# item_2022_Frontend_02.net
KiCad netlist of a schematic drawn in EAGLE
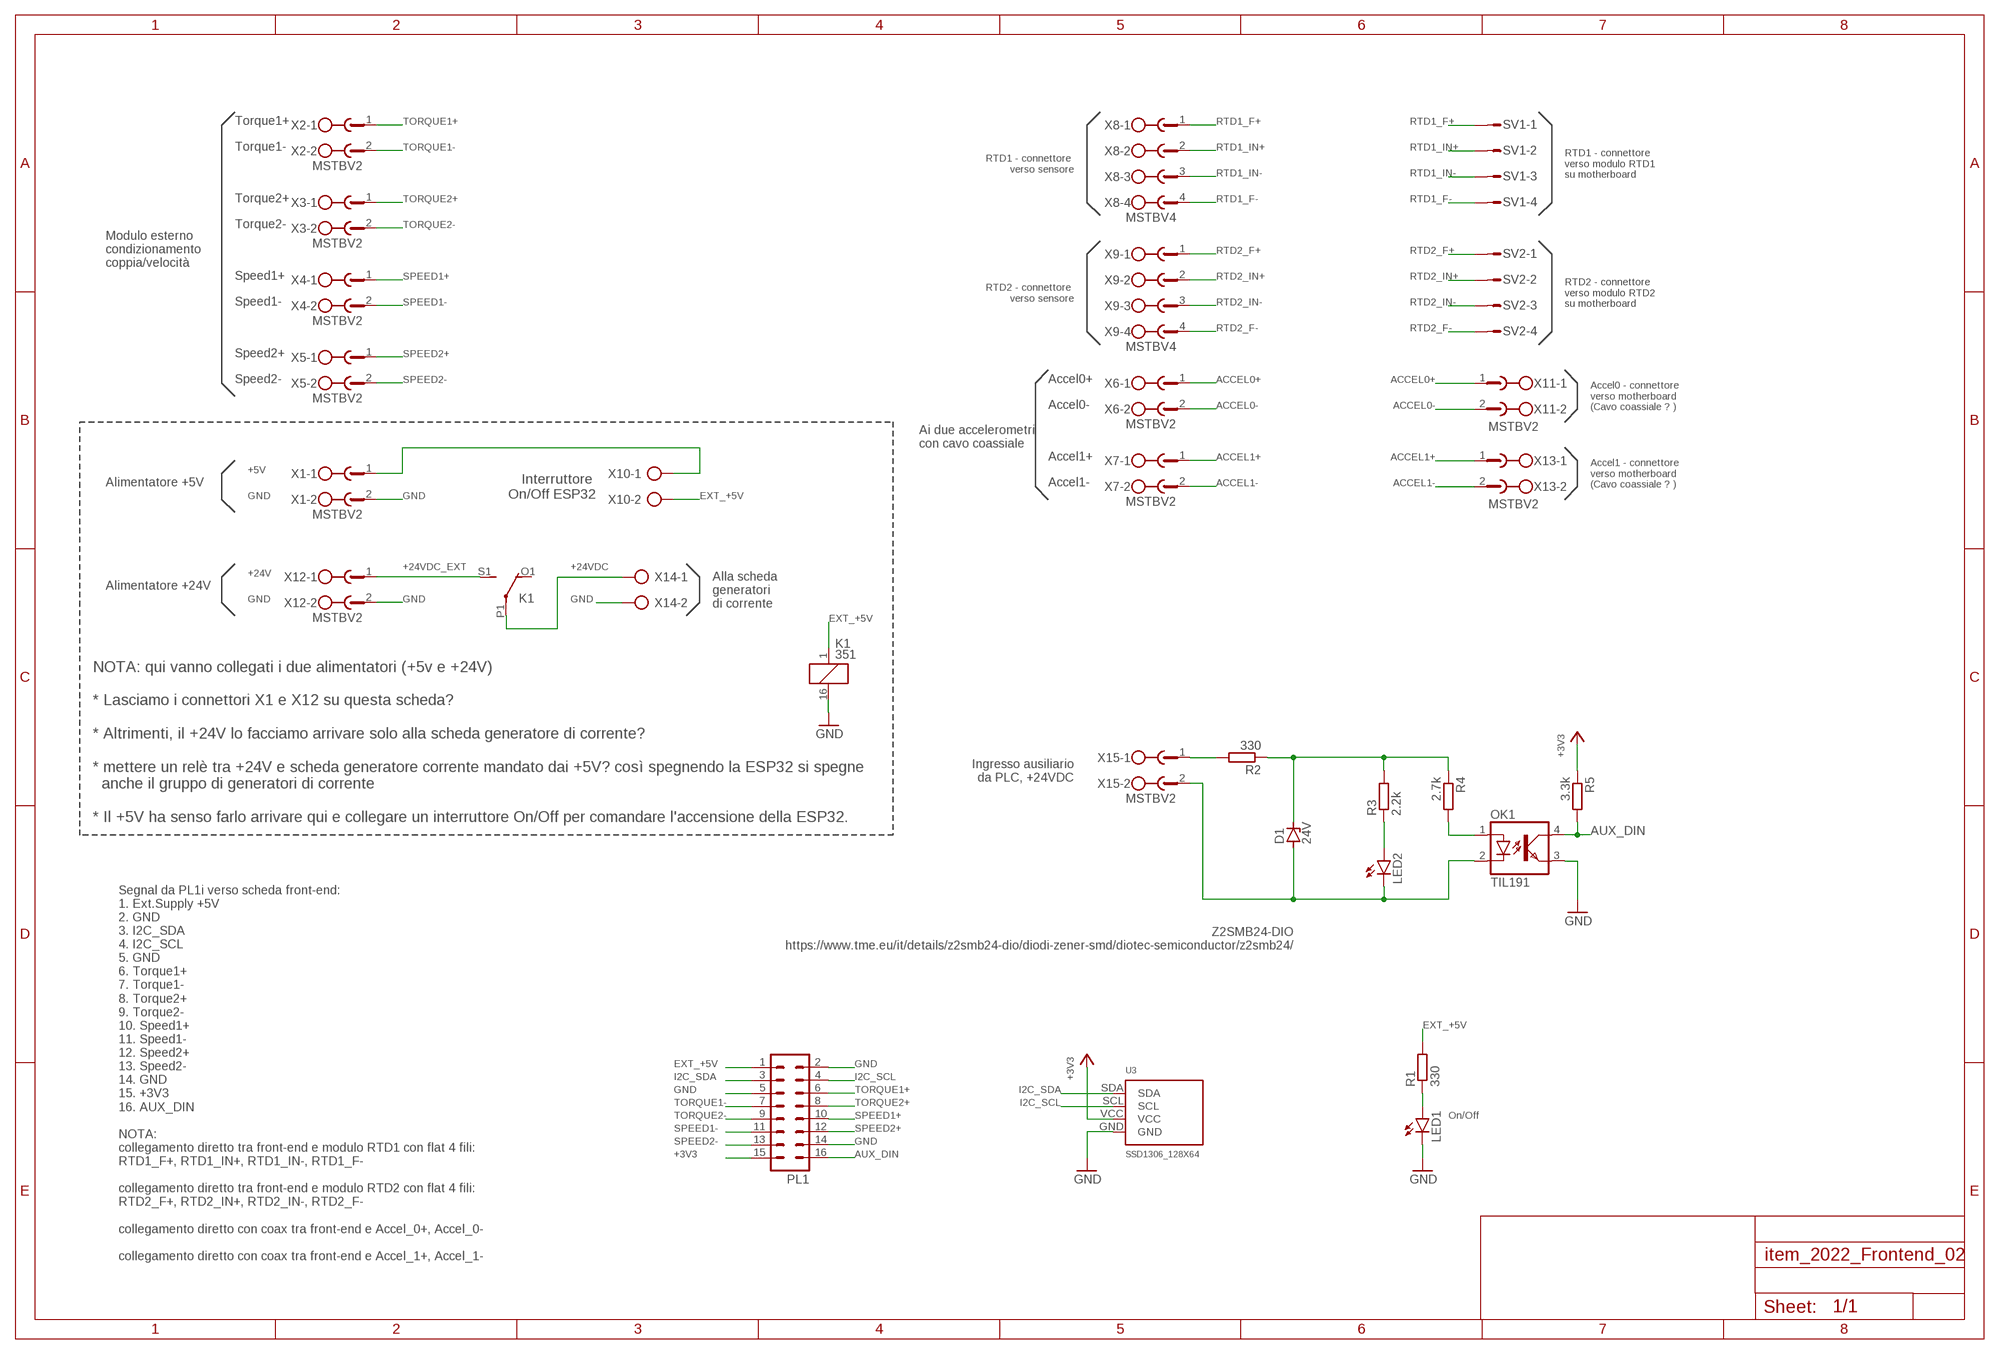
[diagram p0: schematic, sheet 1]

(export (version "E")
  (design (tool "Eeschema 10.0.6"))
  (components
    (comp (ref "D1")
      (value "24V")
      (footprint "eagle-import:SMB")
      (libsource (lib "eagle-import") (part "ZENER-DIODESMB"))
    )
    (comp (ref "K1")
      (value "351")
      (footprint "eagle-import:351")
      (libsource (lib "eagle-import") (part "351"))
    )
    (comp (ref "LED1")
      (value "LED5MM")
      (footprint "eagle-import:LED5MM")
      (libsource (lib "eagle-import") (part "LED5MM"))
    )
    (comp (ref "LED2")
      (value "LED5MM")
      (footprint "eagle-import:LED5MM")
      (libsource (lib "eagle-import") (part "LED5MM"))
    )
    (comp (ref "OK1")
      (value "TIL191")
      (footprint "eagle-import:DIL04")
      (libsource (lib "eagle-import") (part "TIL191"))
    )
    (comp (ref "PL1")
      (value "16V")
      (footprint "eagle-import:16V")
      (libsource (lib "eagle-import") (part "16V"))
    )
    (comp (ref "R1")
      (value "330")
      (footprint "eagle-import:R0805")
      (libsource (lib "eagle-import") (part "R-EU_R0805"))
    )
    (comp (ref "R2")
      (value "330")
      (footprint "eagle-import:R0805")
      (libsource (lib "eagle-import") (part "R-EU_R0805"))
    )
    (comp (ref "R3")
      (value "2.2k")
      (footprint "eagle-import:R0805")
      (libsource (lib "eagle-import") (part "R-EU_R0805"))
    )
    (comp (ref "R4")
      (value "2.7k")
      (footprint "eagle-import:R0805")
      (libsource (lib "eagle-import") (part "R-EU_R0805"))
    )
    (comp (ref "R5")
      (value "3.3k")
      (footprint "eagle-import:R0805")
      (libsource (lib "eagle-import") (part "R-EU_R0805"))
    )
    (comp (ref "SV1")
      (value "S04P")
      (footprint "eagle-import:S04P")
      (libsource (lib "eagle-import") (part "S04P"))
    )
    (comp (ref "SV2")
      (value "S04P")
      (footprint "eagle-import:S04P")
      (libsource (lib "eagle-import") (part "S04P"))
    )
    (comp (ref "U3")
      (value "SSD1306_128X64")
      (footprint "eagle-import:128X64")
      (libsource (lib "eagle-import") (part "SSD1306_128X64"))
    )
    (comp (ref "X1")
      (value "MSTBV2")
      (footprint "eagle-import:MSTBV2")
      (fields (field (name "MPN") "MSTBV 2,5/2-GF-5.08"))
      (libsource (lib "eagle-import") (part "MSTBV2"))
    )
    (comp (ref "X2")
      (value "MSTBV2")
      (footprint "eagle-import:MSTBV2")
      (fields (field (name "MPN") "MSTBV 2,5/2-GF-5.08"))
      (libsource (lib "eagle-import") (part "MSTBV2"))
    )
    (comp (ref "X3")
      (value "MSTBV2")
      (footprint "eagle-import:MSTBV2")
      (fields (field (name "MPN") "MSTBV 2,5/2-GF-5.08"))
      (libsource (lib "eagle-import") (part "MSTBV2"))
    )
    (comp (ref "X4")
      (value "MSTBV2")
      (footprint "eagle-import:MSTBV2")
      (fields (field (name "MPN") "MSTBV 2,5/2-GF-5.08"))
      (libsource (lib "eagle-import") (part "MSTBV2"))
    )
    (comp (ref "X5")
      (value "MSTBV2")
      (footprint "eagle-import:MSTBV2")
      (fields (field (name "MPN") "MSTBV 2,5/2-GF-5.08"))
      (libsource (lib "eagle-import") (part "MSTBV2"))
    )
    (comp (ref "X6")
      (value "MSTBV2")
      (footprint "eagle-import:MSTBV2")
      (fields (field (name "MPN") "MSTBV 2,5/2-GF-5.08"))
      (libsource (lib "eagle-import") (part "MSTBV2"))
    )
    (comp (ref "X7")
      (value "MSTBV2")
      (footprint "eagle-import:MSTBV2")
      (fields (field (name "MPN") "MSTBV 2,5/2-GF-5.08"))
      (libsource (lib "eagle-import") (part "MSTBV2"))
    )
    (comp (ref "X8")
      (value "MSTBV4")
      (footprint "eagle-import:MSTBV4")
      (fields (field (name "MPN") "MSTBV 2,5/4-GF-5.08"))
      (libsource (lib "eagle-import") (part "MSTBV4"))
    )
    (comp (ref "X9")
      (value "MSTBV4")
      (footprint "eagle-import:MSTBV4")
      (fields (field (name "MPN") "MSTBV 2,5/4-GF-5.08"))
      (libsource (lib "eagle-import") (part "MSTBV4"))
    )
    (comp (ref "X10")
      (value "AK500/2")
      (footprint "eagle-import:AK500_2")
      (libsource (lib "eagle-import") (part "AK500/2"))
    )
    (comp (ref "X11")
      (value "MSTBV2")
      (footprint "eagle-import:MSTBV2")
      (fields (field (name "MPN") "MSTBV 2,5/2-GF-5.08"))
      (libsource (lib "eagle-import") (part "MSTBV2"))
    )
    (comp (ref "X12")
      (value "MSTBV2")
      (footprint "eagle-import:MSTBV2")
      (fields (field (name "MPN") "MSTBV 2,5/2-GF-5.08"))
      (libsource (lib "eagle-import") (part "MSTBV2"))
    )
    (comp (ref "X13")
      (value "MSTBV2")
      (footprint "eagle-import:MSTBV2")
      (fields (field (name "MPN") "MSTBV 2,5/2-GF-5.08"))
      (libsource (lib "eagle-import") (part "MSTBV2"))
    )
    (comp (ref "X14")
      (value "AK500/2")
      (footprint "eagle-import:AK500_2")
      (libsource (lib "eagle-import") (part "AK500/2"))
    )
    (comp (ref "X15")
      (value "MSTBV2")
      (footprint "eagle-import:MSTBV2")
      (fields (field (name "MPN") "MSTBV 2,5/2-GF-5.08"))
      (libsource (lib "eagle-import") (part "MSTBV2"))
    )
  )
  (nets
    (net (code "1") (name "+3V3") (class "Default")
      (node (ref "PL1") (pin "15") (pinfunction "15_15") (pintype "passive"))
      (node (ref "R5") (pin "1") (pinfunction "1_1") (pintype "passive"))
      (node (ref "U3") (pin "VCC") (pinfunction "VCC_VCC") (pintype "power_in"))
    )
    (net (code "2") (name "/+24VDC") (class "Default")
      (node (ref "K1") (pin "P1") (pinfunction "P_P1") (pintype "passive"))
      (node (ref "X14") (pin "1") (pinfunction "KL_1") (pintype "passive"))
    )
    (net (code "3") (name "/+24VDC_EXT") (class "Default")
      (node (ref "K1") (pin "S1") (pinfunction "S_S1") (pintype "passive"))
      (node (ref "X12") (pin "1") (pinfunction "1_1") (pintype "passive"))
    )
    (net (code "4") (name "/ACCEL0+") (class "Default")
      (node (ref "X11") (pin "1") (pinfunction "1_1") (pintype "passive"))
      (node (ref "X6") (pin "1") (pinfunction "1_1") (pintype "passive"))
    )
    (net (code "5") (name "/ACCEL0-") (class "Default")
      (node (ref "X11") (pin "2") (pinfunction "1_2") (pintype "passive"))
      (node (ref "X6") (pin "2") (pinfunction "1_2") (pintype "passive"))
    )
    (net (code "6") (name "/ACCEL1+") (class "Default")
      (node (ref "X13") (pin "1") (pinfunction "1_1") (pintype "passive"))
      (node (ref "X7") (pin "1") (pinfunction "1_1") (pintype "passive"))
    )
    (net (code "7") (name "/ACCEL1-") (class "Default")
      (node (ref "X13") (pin "2") (pinfunction "1_2") (pintype "passive"))
      (node (ref "X7") (pin "2") (pinfunction "1_2") (pintype "passive"))
    )
    (net (code "8") (name "/AUX_DIN") (class "Default")
      (node (ref "OK1") (pin "4") (pinfunction "COL_4") (pintype "passive"))
      (node (ref "PL1") (pin "16") (pinfunction "16_16") (pintype "passive"))
      (node (ref "R5") (pin "2") (pinfunction "2_2") (pintype "passive"))
    )
    (net (code "9") (name "/EXT_+5V") (class "Default")
      (node (ref "K1") (pin "1") (pinfunction "1_1") (pintype "passive"))
      (node (ref "PL1") (pin "1") (pinfunction "1_1") (pintype "passive"))
      (node (ref "R1") (pin "2") (pinfunction "2_2") (pintype "passive"))
      (node (ref "X10") (pin "2") (pinfunction "KL_2") (pintype "passive"))
    )
    (net (code "10") (name "/I2C_SCL") (class "Default")
      (node (ref "PL1") (pin "4") (pinfunction "4_4") (pintype "passive"))
      (node (ref "U3") (pin "SCL") (pinfunction "SCL_SCL") (pintype "bidirectional"))
    )
    (net (code "11") (name "/I2C_SDA") (class "Default")
      (node (ref "PL1") (pin "3") (pinfunction "3_3") (pintype "passive"))
      (node (ref "U3") (pin "SDA") (pinfunction "SDA_SDA") (pintype "bidirectional"))
    )
    (net (code "12") (name "/RTD1_F+") (class "Default")
      (node (ref "SV1") (pin "1") (pinfunction "S_1") (pintype "passive"))
      (node (ref "X8") (pin "1") (pinfunction "1_1") (pintype "passive"))
    )
    (net (code "13") (name "/RTD1_F-") (class "Default")
      (node (ref "SV1") (pin "4") (pinfunction "S_4") (pintype "passive"))
      (node (ref "X8") (pin "4") (pinfunction "1_4") (pintype "passive"))
    )
    (net (code "14") (name "/RTD1_IN+") (class "Default")
      (node (ref "SV1") (pin "2") (pinfunction "S_2") (pintype "passive"))
      (node (ref "X8") (pin "2") (pinfunction "1_2") (pintype "passive"))
    )
    (net (code "15") (name "/RTD1_IN-") (class "Default")
      (node (ref "SV1") (pin "3") (pinfunction "S_3") (pintype "passive"))
      (node (ref "X8") (pin "3") (pinfunction "1_3") (pintype "passive"))
    )
    (net (code "16") (name "/RTD2_F+") (class "Default")
      (node (ref "SV2") (pin "1") (pinfunction "S_1") (pintype "passive"))
      (node (ref "X9") (pin "1") (pinfunction "1_1") (pintype "passive"))
    )
    (net (code "17") (name "/RTD2_F-") (class "Default")
      (node (ref "SV2") (pin "4") (pinfunction "S_4") (pintype "passive"))
      (node (ref "X9") (pin "4") (pinfunction "1_4") (pintype "passive"))
    )
    (net (code "18") (name "/RTD2_IN+") (class "Default")
      (node (ref "SV2") (pin "2") (pinfunction "S_2") (pintype "passive"))
      (node (ref "X9") (pin "2") (pinfunction "1_2") (pintype "passive"))
    )
    (net (code "19") (name "/RTD2_IN-") (class "Default")
      (node (ref "SV2") (pin "3") (pinfunction "S_3") (pintype "passive"))
      (node (ref "X9") (pin "3") (pinfunction "1_3") (pintype "passive"))
    )
    (net (code "20") (name "/SPEED1+") (class "Default")
      (node (ref "PL1") (pin "10") (pinfunction "10_10") (pintype "passive"))
      (node (ref "X4") (pin "1") (pinfunction "1_1") (pintype "passive"))
    )
    (net (code "21") (name "/SPEED1-") (class "Default")
      (node (ref "PL1") (pin "11") (pinfunction "11_11") (pintype "passive"))
      (node (ref "X4") (pin "2") (pinfunction "1_2") (pintype "passive"))
    )
    (net (code "22") (name "/SPEED2+") (class "Default")
      (node (ref "PL1") (pin "12") (pinfunction "12_12") (pintype "passive"))
      (node (ref "X5") (pin "1") (pinfunction "1_1") (pintype "passive"))
    )
    (net (code "23") (name "/SPEED2-") (class "Default")
      (node (ref "PL1") (pin "13") (pinfunction "13_13") (pintype "passive"))
      (node (ref "X5") (pin "2") (pinfunction "1_2") (pintype "passive"))
    )
    (net (code "24") (name "/TORQUE1+") (class "Default")
      (node (ref "PL1") (pin "6") (pinfunction "6_6") (pintype "passive"))
      (node (ref "X2") (pin "1") (pinfunction "1_1") (pintype "passive"))
    )
    (net (code "25") (name "/TORQUE1-") (class "Default")
      (node (ref "PL1") (pin "7") (pinfunction "7_7") (pintype "passive"))
      (node (ref "X2") (pin "2") (pinfunction "1_2") (pintype "passive"))
    )
    (net (code "26") (name "/TORQUE2+") (class "Default")
      (node (ref "PL1") (pin "8") (pinfunction "8_8") (pintype "passive"))
      (node (ref "X3") (pin "1") (pinfunction "1_1") (pintype "passive"))
    )
    (net (code "27") (name "/TORQUE2-") (class "Default")
      (node (ref "PL1") (pin "9") (pinfunction "9_9") (pintype "passive"))
      (node (ref "X3") (pin "2") (pinfunction "1_2") (pintype "passive"))
    )
    (net (code "28") (name "GND") (class "Default")
      (node (ref "K1") (pin "16") (pinfunction "2_16") (pintype "passive"))
      (node (ref "LED1") (pin "K") (pinfunction "C_K") (pintype "passive"))
      (node (ref "OK1") (pin "3") (pinfunction "EMIT_3") (pintype "passive"))
      (node (ref "PL1") (pin "14") (pinfunction "14_14") (pintype "passive"))
      (node (ref "PL1") (pin "2") (pinfunction "2_2") (pintype "passive"))
      (node (ref "PL1") (pin "5") (pinfunction "5_5") (pintype "passive"))
      (node (ref "U3") (pin "GND") (pinfunction "GND_GND") (pintype "power_in"))
      (node (ref "X1") (pin "2") (pinfunction "1_2") (pintype "passive"))
      (node (ref "X12") (pin "2") (pinfunction "1_2") (pintype "passive"))
      (node (ref "X14") (pin "2") (pinfunction "KL_2") (pintype "passive"))
    )
    (net (code "29") (name "Net-(D1-PadC)") (class "Default")
      (node (ref "D1") (pin "C") (pinfunction "C_C") (pintype "passive"))
      (node (ref "R2") (pin "1") (pinfunction "1_1") (pintype "passive"))
      (node (ref "R3") (pin "2") (pinfunction "2_2") (pintype "passive"))
      (node (ref "R4") (pin "1") (pinfunction "1_1") (pintype "passive"))
    )
    (net (code "30") (name "Net-(LED1-PadA)") (class "Default")
      (node (ref "LED1") (pin "A") (pinfunction "A_A") (pintype "passive"))
      (node (ref "R1") (pin "1") (pinfunction "1_1") (pintype "passive"))
    )
    (net (code "31") (name "Net-(LED2-C)") (class "Default")
      (node (ref "D1") (pin "A") (pinfunction "A_A") (pintype "passive"))
      (node (ref "LED2") (pin "K") (pinfunction "C_K") (pintype "passive"))
      (node (ref "OK1") (pin "2") (pinfunction "C_2") (pintype "passive"))
      (node (ref "X15") (pin "2") (pinfunction "1_2") (pintype "passive"))
    )
    (net (code "32") (name "Net-(LED2-PadA)") (class "Default")
      (node (ref "LED2") (pin "A") (pinfunction "A_A") (pintype "passive"))
      (node (ref "R3") (pin "1") (pinfunction "1_1") (pintype "passive"))
    )
    (net (code "33") (name "Net-(OK1-A)") (class "Default")
      (node (ref "OK1") (pin "1") (pinfunction "A_1") (pintype "passive"))
      (node (ref "R4") (pin "2") (pinfunction "2_2") (pintype "passive"))
    )
    (net (code "34") (name "Net-(R2-Pad2)") (class "Default")
      (node (ref "R2") (pin "2") (pinfunction "2_2") (pintype "passive"))
      (node (ref "X15") (pin "1") (pinfunction "1_1") (pintype "passive"))
    )
    (net (code "35") (name "Net-(X10A-KL)") (class "Default")
      (node (ref "X1") (pin "1") (pinfunction "1_1") (pintype "passive"))
      (node (ref "X10") (pin "1") (pinfunction "KL_1") (pintype "passive"))
    )
    (net (code "36") (name "unconnected-(K1B-O-PadO1)") (class "Default")
      (node (ref "K1") (pin "O1") (pinfunction "O_O1") (pintype "passive"))
    )
  )
)
